# V1_0.net
KiCad netlist of a schematic drawn in Altium Designer
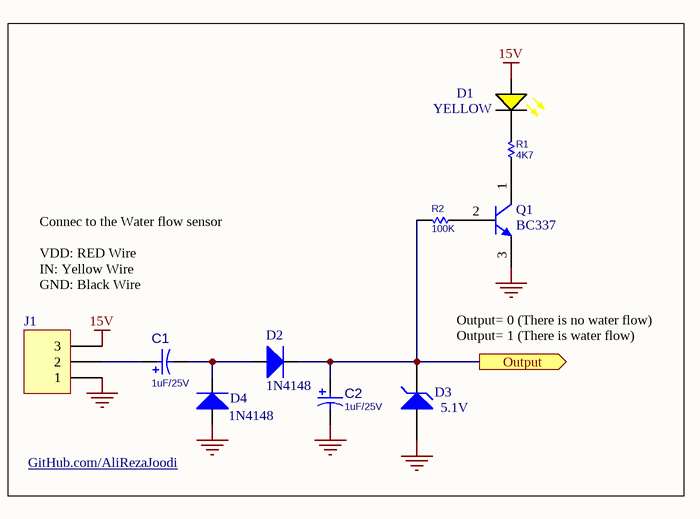
[diagram p0: V1.0.SchDoc]

(export (version "E")
  (design (tool "Eeschema 10.0.6"))
  (components
    (comp (ref "C1")
      (value "1uF/25V")
      (footprint "C_THD_EL_(P2.54-D6-H11)")
      (description "Capacitor, Electrolytic")
      (libsource (lib "Passive") (part "Capacitor_Electrolytic"))
    )
    (comp (ref "C2")
      (value "1uF/25V")
      (footprint "C_THD_EL_(P2.54-D6-H11)")
      (description "Capacitor, Electrolytic")
      (libsource (lib "Passive") (part "Capacitor_Electrolytic"))
    )
    (comp (ref "D1")
      (value "YELLOW")
      (footprint "LED_THD_5MM_YELLOW")
      (description "LED, Yellow")
      (fields (field (name "MANUFACTURER") "Generic Components") (field (name "PUBLISHER") "Altium Limited"))
      (libsource (lib "Display") (part "LED_YELLOW"))
    )
    (comp (ref "D2")
      (value "1N4148")
      (footprint "D_THD_AXIAL0.3_DO-35")
      (description "Default Diode")
      (fields (field (name "MANUFACTURER") "Generic Components") (field (name "PUBLISHER") "Altium Limited"))
      (libsource (lib "Miscellaneous Devices") (part "Diode"))
    )
    (comp (ref "D3")
      (value "5.1V")
      (footprint "D_THD_AXIAL0.3_DO-35")
      (description "Zener Diode")
      (fields (field (name "MANUFACTURER") "Generic Components") (field (name "PUBLISHER") "Altium Limited"))
      (libsource (lib "Miscellaneous Devices") (part "D Zener"))
    )
    (comp (ref "D4")
      (value "1N4148")
      (footprint "D_THD_AXIAL0.3_DO-35")
      (description "Default Diode")
      (fields (field (name "MANUFACTURER") "Generic Components") (field (name "PUBLISHER") "Altium Limited"))
      (libsource (lib "Miscellaneous Devices") (part "Diode"))
    )
    (comp (ref "J1")
      (value "J8")
      (footprint "Connector_Phoenix_3PIN_MSTB")
      (description "Header, 3-Pin")
      (fields (field (name "MANUFACTURER") "Generic Components") (field (name "PUBLISHER") "Altium Limited"))
      (libsource (lib "Miscellaneous Connectors") (part "Header 3"))
    )
    (comp (ref "Q1")
      (value "BC337")
      (footprint "TO92_3Pin_Form3")
      (description "Transistor, BJT, NPN")
      (libsource (lib "Passive") (part "Transistor_BJT_NPN"))
    )
    (comp (ref "R1")
      (value "4K7")
      (footprint "R_THD_AXIAL0.4(1/4W)")
      (description "Resistor,")
      (libsource (lib "Passive") (part "Resistor"))
    )
    (comp (ref "R2")
      (value "100K")
      (footprint "R_THD_AXIAL0.4(1/4W)")
      (description "Resistor,")
      (libsource (lib "Passive") (part "Resistor"))
    )
  )
  (nets
    (net (code "1") (name "/Output") (class "Default")
      (node (ref "C2") (pin "1") (pinfunction "1_1") (pintype "passive"))
      (node (ref "D2") (pin "2") (pinfunction "K_2") (pintype "passive"))
      (node (ref "D3") (pin "2") (pinfunction "K_2") (pintype "passive"))
      (node (ref "R2") (pin "1") (pinfunction "1_1") (pintype "passive"))
    )
    (net (code "2") (name "15V") (class "Default")
      (node (ref "D1") (pin "1") (pinfunction "A_1") (pintype "passive"))
      (node (ref "J1") (pin "3") (pinfunction "3_3") (pintype "passive"))
    )
    (net (code "3") (name "GND") (class "Default")
      (node (ref "C2") (pin "2") (pinfunction "2_2") (pintype "passive"))
      (node (ref "D3") (pin "1") (pinfunction "A_1") (pintype "passive"))
      (node (ref "D4") (pin "1") (pinfunction "A_1") (pintype "passive"))
      (node (ref "J1") (pin "1") (pinfunction "1_1") (pintype "passive"))
      (node (ref "Q1") (pin "3") (pinfunction "E_3") (pintype "passive"))
    )
    (net (code "4") (name "Net-(C1-Pad1)") (class "Default")
      (node (ref "C1") (pin "1") (pinfunction "1_1") (pintype "passive"))
      (node (ref "J1") (pin "2") (pinfunction "2_2") (pintype "passive"))
    )
    (net (code "5") (name "Net-(D1-K)") (class "Default")
      (node (ref "D1") (pin "2") (pinfunction "K_2") (pintype "passive"))
      (node (ref "R1") (pin "1") (pinfunction "1_1") (pintype "passive"))
    )
    (net (code "6") (name "Net-(D2-A)") (class "Default")
      (node (ref "C1") (pin "2") (pinfunction "2_2") (pintype "passive"))
      (node (ref "D2") (pin "1") (pinfunction "A_1") (pintype "passive"))
      (node (ref "D4") (pin "2") (pinfunction "K_2") (pintype "passive"))
    )
    (net (code "7") (name "Net-(Q1-B)") (class "Default")
      (node (ref "Q1") (pin "2") (pinfunction "B_2") (pintype "passive"))
      (node (ref "R2") (pin "2") (pinfunction "2_2") (pintype "passive"))
    )
    (net (code "8") (name "Net-(Q1-C)") (class "Default")
      (node (ref "Q1") (pin "1") (pinfunction "C_1") (pintype "passive"))
      (node (ref "R1") (pin "2") (pinfunction "2_2") (pintype "passive"))
    )
  )
)
